# Sensor_Board.net
KiCad netlist of a schematic drawn in EAGLE
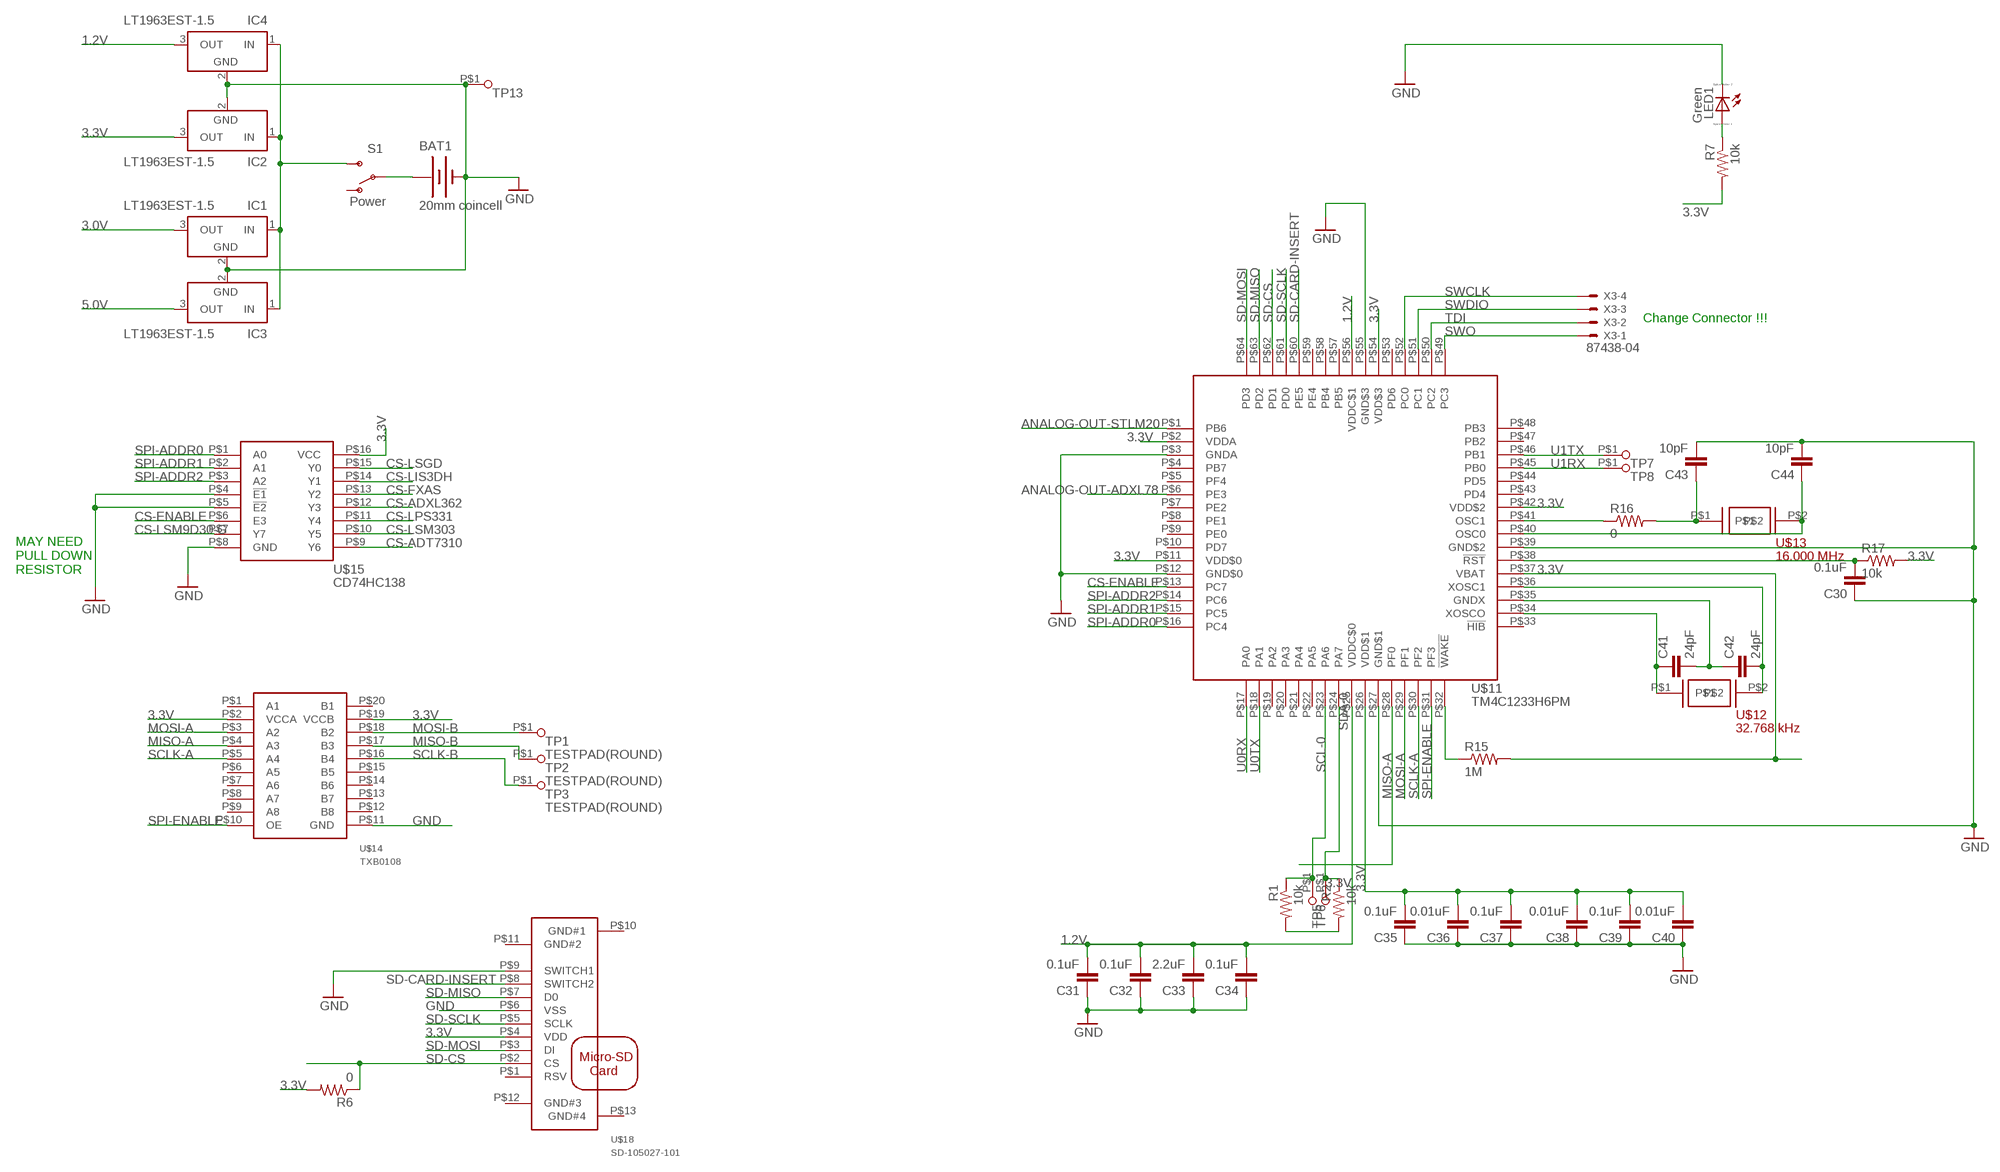
[diagram p0: schematic, sheet 1]
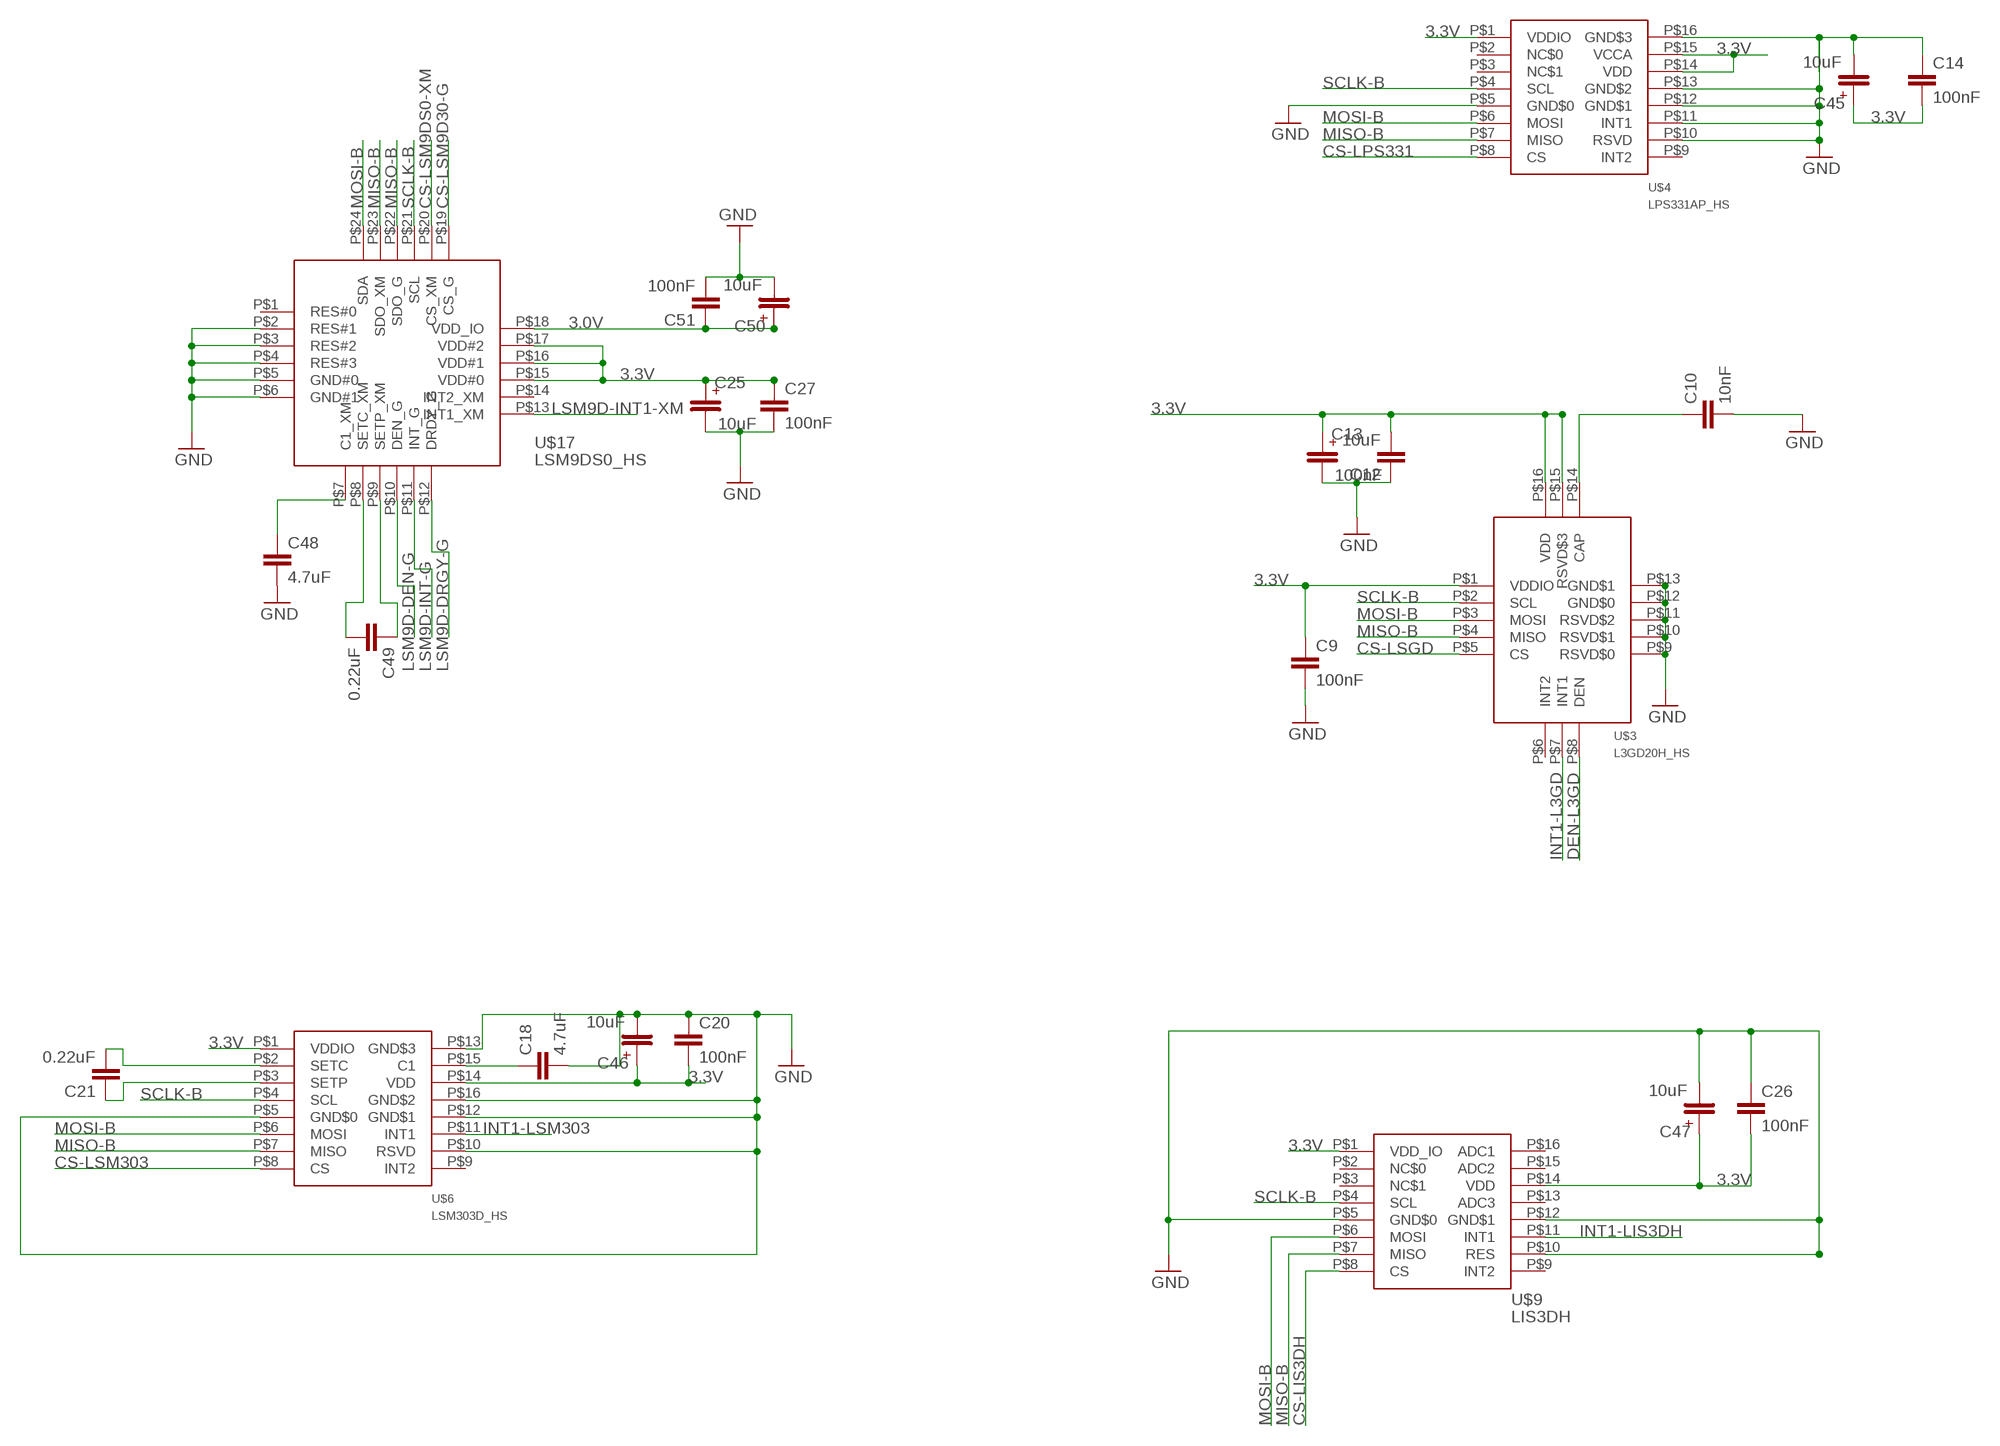
[diagram p1: schematic, sheet 2]
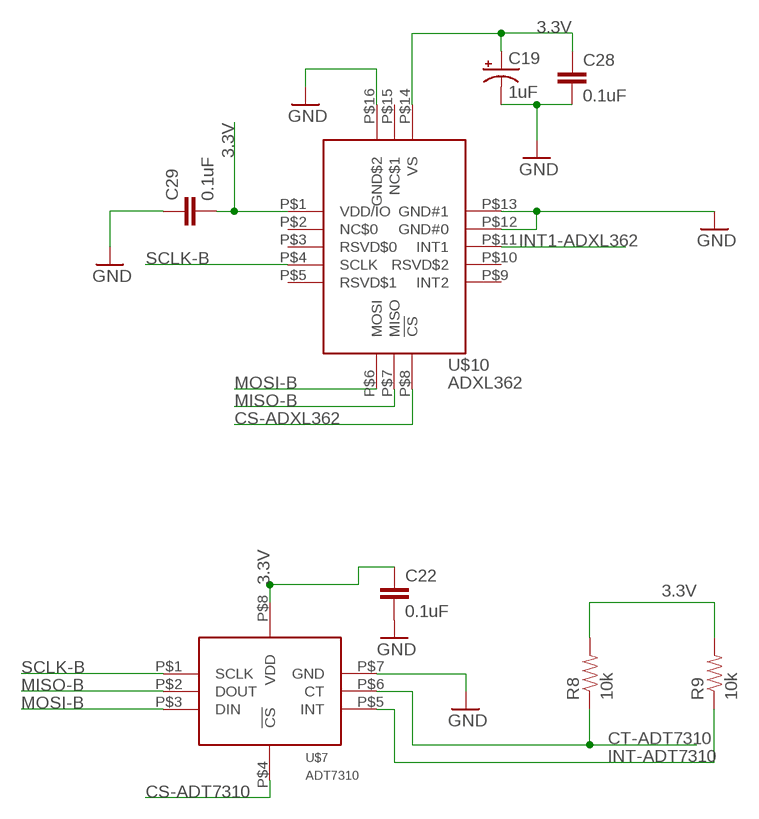
[diagram p2: schematic, sheet 3]
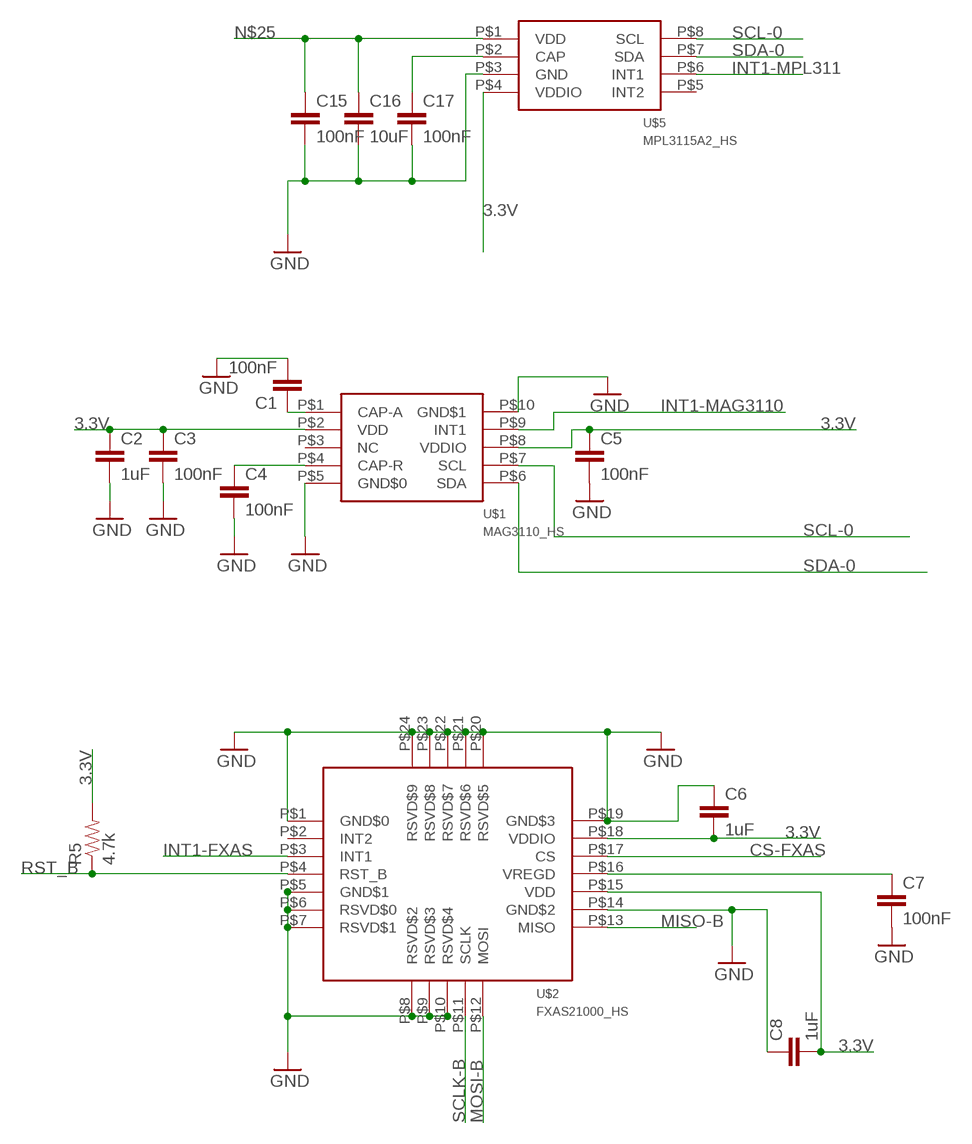
[diagram p3: schematic, sheet 4]
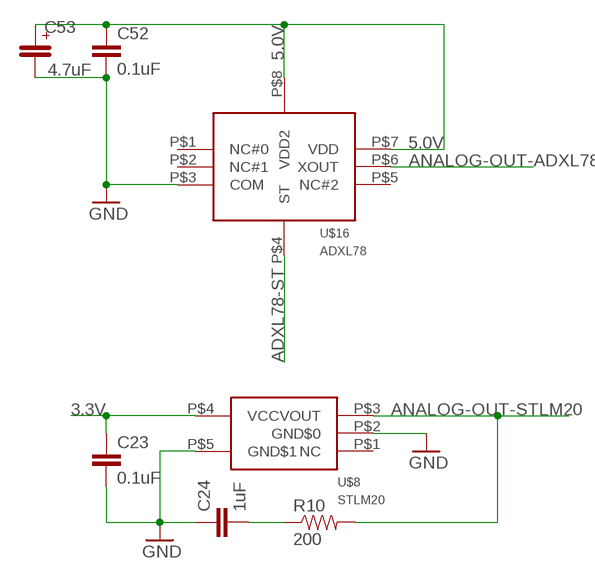
[diagram p4: schematic, sheet 5]

(export (version "E")
  (design (tool "Eeschema 10.0.6"))
  (components
    (comp (ref "C9")
      (value "100nF")
      (footprint "eagle-import:0603-CAP")
      (libsource (lib "eagle-import") (part "CAP0603-CAP"))
    )
    (comp (ref "C10")
      (value "10nF")
      (footprint "eagle-import:0603-CAP")
      (libsource (lib "eagle-import") (part "CAP0603-CAP"))
    )
    (comp (ref "C12")
      (value "10uF")
      (footprint "eagle-import:0603-CAP")
      (libsource (lib "eagle-import") (part "CAP0603-CAP"))
    )
    (comp (ref "C13")
      (value "100nF")
      (footprint "eagle-import:4.3X7.3SMD")
      (libsource (lib "eagle-import") (part "EEFCD0J100ER"))
    )
    (comp (ref "C14")
      (value "100nF")
      (footprint "eagle-import:0603-CAP")
      (libsource (lib "eagle-import") (part "CAP0603-CAP"))
    )
    (comp (ref "C18")
      (value "4.7uF")
      (footprint "eagle-import:0603-CAP")
      (libsource (lib "eagle-import") (part "CAP0603-CAP"))
    )
    (comp (ref "C20")
      (value "100nF")
      (footprint "eagle-import:0603-CAP")
      (libsource (lib "eagle-import") (part "CAP0603-CAP"))
    )
    (comp (ref "C21")
      (value "0.22uF")
      (footprint "eagle-import:0603-CAP")
      (libsource (lib "eagle-import") (part "CAP0603-CAP"))
    )
    (comp (ref "C25")
      (value "10uF")
      (footprint "eagle-import:4.3X7.3SMD")
      (libsource (lib "eagle-import") (part "EEFCD0J100ER"))
    )
    (comp (ref "C26")
      (value "100nF")
      (footprint "eagle-import:0603-CAP")
      (libsource (lib "eagle-import") (part "CAP0603-CAP"))
    )
    (comp (ref "C27")
      (value "100nF")
      (footprint "eagle-import:0603-CAP")
      (libsource (lib "eagle-import") (part "CAP0603-CAP"))
    )
    (comp (ref "C45")
      (value "10uF")
      (footprint "eagle-import:4.3X7.3SMD")
      (libsource (lib "eagle-import") (part "EEFCD0J100ER"))
    )
    (comp (ref "C46")
      (value "10uF")
      (footprint "eagle-import:4.3X7.3SMD")
      (libsource (lib "eagle-import") (part "EEFCD0J100ER"))
    )
    (comp (ref "C47")
      (value "10uF")
      (footprint "eagle-import:4.3X7.3SMD")
      (libsource (lib "eagle-import") (part "EEFCD0J100ER"))
    )
    (comp (ref "C48")
      (value "4.7uF")
      (footprint "eagle-import:0603-CAP")
      (libsource (lib "eagle-import") (part "CAP0603-CAP"))
    )
    (comp (ref "C49")
      (value "0.22uF")
      (footprint "eagle-import:0603-CAP")
      (libsource (lib "eagle-import") (part "CAP0603-CAP"))
    )
    (comp (ref "C50")
      (value "10uF")
      (footprint "eagle-import:4.3X7.3SMD")
      (libsource (lib "eagle-import") (part "EEFCD0J100ER"))
    )
    (comp (ref "C51")
      (value "100nF")
      (footprint "eagle-import:0603-CAP")
      (libsource (lib "eagle-import") (part "CAP0603-CAP"))
    )
    (comp (ref "U$3")
      (value "L3GD20H_HS")
      (footprint "eagle-import:LGA-16(3X3)_HS")
      (libsource (lib "eagle-import") (part "L3GD20H_HS"))
    )
    (comp (ref "U$4")
      (value "LPS331AP_HS")
      (footprint "eagle-import:LGA-16(3X3)_HS")
      (libsource (lib "eagle-import") (part "LPS331AP_HS"))
    )
    (comp (ref "U$6")
      (value "LSM303D_HS")
      (footprint "eagle-import:LGA-16(3X3)_HS")
      (libsource (lib "eagle-import") (part "LSM303D_HS"))
    )
    (comp (ref "U$9")
      (value "LIS3DH")
      (footprint "eagle-import:LGA-16(3X3)_HS")
      (libsource (lib "eagle-import") (part "LIS3DH_HS"))
    )
    (comp (ref "U$17")
      (value "LSM9DS0_HS")
      (footprint "eagle-import:LGA-24(4X4)_HS")
      (libsource (lib "eagle-import") (part "LSM9DS0_HS"))
    )
    (comp (ref "BAT1")
      (value "20mm coincell")
      (footprint "eagle-import:BATTCON_20MM_4LEGS")
      (libsource (lib "eagle-import") (part "BATTERY20MM_4LEGS"))
    )
    (comp (ref "C30")
      (value "0.1uF")
      (footprint "eagle-import:0603-CAP")
      (libsource (lib "eagle-import") (part "CAP0603-CAP"))
    )
    (comp (ref "C31")
      (value "0.1uF")
      (footprint "eagle-import:0603-CAP")
      (libsource (lib "eagle-import") (part "CAP0603-CAP"))
    )
    (comp (ref "C32")
      (value "0.1uF")
      (footprint "eagle-import:0603-CAP")
      (libsource (lib "eagle-import") (part "CAP0603-CAP"))
    )
    (comp (ref "C33")
      (value "2.2uF")
      (footprint "eagle-import:0603-CAP")
      (libsource (lib "eagle-import") (part "CAP0603-CAP"))
    )
    (comp (ref "C34")
      (value "0.1uF")
      (footprint "eagle-import:0603-CAP")
      (libsource (lib "eagle-import") (part "CAP0603-CAP"))
    )
    (comp (ref "C35")
      (value "0.1uF")
      (footprint "eagle-import:0603-CAP")
      (libsource (lib "eagle-import") (part "CAP0603-CAP"))
    )
    (comp (ref "C36")
      (value "0.01uF")
      (footprint "eagle-import:0603-CAP")
      (libsource (lib "eagle-import") (part "CAP0603-CAP"))
    )
    (comp (ref "C37")
      (value "0.1uF")
      (footprint "eagle-import:0603-CAP")
      (libsource (lib "eagle-import") (part "CAP0603-CAP"))
    )
    (comp (ref "C38")
      (value "0.01uF")
      (footprint "eagle-import:0603-CAP")
      (libsource (lib "eagle-import") (part "CAP0603-CAP"))
    )
    (comp (ref "C39")
      (value "0.1uF")
      (footprint "eagle-import:0603-CAP")
      (libsource (lib "eagle-import") (part "CAP0603-CAP"))
    )
    (comp (ref "C40")
      (value "0.01uF")
      (footprint "eagle-import:0603-CAP")
      (libsource (lib "eagle-import") (part "CAP0603-CAP"))
    )
    (comp (ref "C41")
      (value "24pF")
      (footprint "eagle-import:0603-CAP")
      (libsource (lib "eagle-import") (part "CAP0603-CAP"))
    )
    (comp (ref "C42")
      (value "24pF")
      (footprint "eagle-import:0603-CAP")
      (libsource (lib "eagle-import") (part "CAP0603-CAP"))
    )
    (comp (ref "C43")
      (value "10pF")
      (footprint "eagle-import:0603-CAP")
      (libsource (lib "eagle-import") (part "CAP0603-CAP"))
    )
    (comp (ref "C44")
      (value "10pF")
      (footprint "eagle-import:0603-CAP")
      (libsource (lib "eagle-import") (part "CAP0603-CAP"))
    )
    (comp (ref "IC1")
      (value "LT1963EST-1.5")
      (footprint "eagle-import:SOT223")
      (libsource (lib "eagle-import") (part "LT1963EST-1.5"))
    )
    (comp (ref "IC2")
      (value "LT1963EST-1.5")
      (footprint "eagle-import:SOT223")
      (libsource (lib "eagle-import") (part "LT1963EST-1.5"))
    )
    (comp (ref "IC3")
      (value "LT1963EST-1.5")
      (footprint "eagle-import:SOT223")
      (libsource (lib "eagle-import") (part "LT1963EST-1.5"))
    )
    (comp (ref "IC4")
      (value "LT1963EST-1.5")
      (footprint "eagle-import:SOT223")
      (libsource (lib "eagle-import") (part "LT1963EST-1.5"))
    )
    (comp (ref "LED1")
      (value "Green")
      (footprint "eagle-import:LED_SML0603")
      (libsource (lib "eagle-import") (part "LED_ESML0603"))
    )
    (comp (ref "R1")
      (value "10k")
      (footprint "eagle-import:0603-RES")
      (libsource (lib "eagle-import") (part "RESISTOR0603-RES"))
    )
    (comp (ref "R2")
      (value "10k")
      (footprint "eagle-import:0603-RES")
      (libsource (lib "eagle-import") (part "RESISTOR0603-RES"))
    )
    (comp (ref "R6")
      (value "0")
      (footprint "eagle-import:0603-RES")
      (libsource (lib "eagle-import") (part "RESISTOR0603-RES"))
    )
    (comp (ref "R7")
      (value "10k")
      (footprint "eagle-import:0603-RES")
      (libsource (lib "eagle-import") (part "RESISTOR0603-RES"))
    )
    (comp (ref "R15")
      (value "1M")
      (footprint "eagle-import:0603-RES")
      (libsource (lib "eagle-import") (part "RESISTOR0603-RES"))
    )
    (comp (ref "R16")
      (value "0")
      (footprint "eagle-import:0603-RES")
      (libsource (lib "eagle-import") (part "RESISTOR0603-RES"))
    )
    (comp (ref "R17")
      (value "10k")
      (footprint "eagle-import:0603-RES")
      (libsource (lib "eagle-import") (part "RESISTOR0603-RES"))
    )
    (comp (ref "S1")
      (value "Power")
      (footprint "eagle-import:SWITCH-SPST-SMD-A")
      (libsource (lib "eagle-import") (part "SWITCH-SPDT-SMD-A"))
    )
    (comp (ref "TP1")
      (value "TESTPAD(ROUND)")
      (footprint "eagle-import:TESTPAD(ROUND)")
      (libsource (lib "eagle-import") (part "TESTPAD(ROUND)"))
    )
    (comp (ref "TP2")
      (value "TESTPAD(ROUND)")
      (footprint "eagle-import:TESTPAD(ROUND)")
      (libsource (lib "eagle-import") (part "TESTPAD(ROUND)"))
    )
    (comp (ref "TP3")
      (value "TESTPAD(ROUND)")
      (footprint "eagle-import:TESTPAD(ROUND)")
      (libsource (lib "eagle-import") (part "TESTPAD(ROUND)"))
    )
    (comp (ref "TP5")
      (value "TESTPAD(ROUND)")
      (footprint "eagle-import:TESTPAD(ROUND)")
      (libsource (lib "eagle-import") (part "TESTPAD(ROUND)"))
    )
    (comp (ref "TP6")
      (value "TESTPAD(ROUND)")
      (footprint "eagle-import:TESTPAD(ROUND)")
      (libsource (lib "eagle-import") (part "TESTPAD(ROUND)"))
    )
    (comp (ref "TP7")
      (value "TESTPAD(ROUND)")
      (footprint "eagle-import:TESTPAD(ROUND)")
      (libsource (lib "eagle-import") (part "TESTPAD(ROUND)"))
    )
    (comp (ref "TP8")
      (value "TESTPAD(ROUND)")
      (footprint "eagle-import:TESTPAD(ROUND)")
      (libsource (lib "eagle-import") (part "TESTPAD(ROUND)"))
    )
    (comp (ref "TP13")
      (value "TESTPAD(ROUND)")
      (footprint "eagle-import:TESTPAD(ROUND)")
      (libsource (lib "eagle-import") (part "TESTPAD(ROUND)"))
    )
    (comp (ref "U$11")
      (value "TM4C1233H6PM")
      (footprint "eagle-import:S-PQFP-G64")
      (libsource (lib "eagle-import") (part "TM4C1233H6PM"))
    )
    (comp (ref "U$12")
      (value "32.768 kHz")
      (footprint "eagle-import:CYLINDRICAL-(1.9DIAX6L)")
      (libsource (lib "eagle-import") (part "AB26TRB"))
    )
    (comp (ref "U$13")
      (value "16.000 MHz")
      (footprint "eagle-import:2-SMD")
      (libsource (lib "eagle-import") (part "NX5032GA"))
    )
    (comp (ref "U$14")
      (value "TXB0108")
      (footprint "eagle-import:TSSOP-(PW)-20")
      (libsource (lib "eagle-import") (part "TXB0108"))
    )
    (comp (ref "U$15")
      (value "CD74HC138")
      (footprint "eagle-import:SOIC-16")
      (libsource (lib "eagle-import") (part "CD74HC138"))
    )
    (comp (ref "U$18")
      (value "SD-105027-101")
      (footprint "eagle-import:SD-105027-101")
      (libsource (lib "eagle-import") (part "SD-105027-101"))
    )
    (comp (ref "X3")
      (value "87438-04")
      (footprint "eagle-import:87438-04")
      (libsource (lib "eagle-import") (part "87438-04"))
    )
    (comp (ref "C1")
      (value "100nF")
      (footprint "eagle-import:0603-CAP")
      (libsource (lib "eagle-import") (part "CAP0603-CAP"))
    )
    (comp (ref "C2")
      (value "1uF")
      (footprint "eagle-import:0603-CAP")
      (libsource (lib "eagle-import") (part "CAP0603-CAP"))
    )
    (comp (ref "C3")
      (value "100nF")
      (footprint "eagle-import:0603-CAP")
      (libsource (lib "eagle-import") (part "CAP0603-CAP"))
    )
    (comp (ref "C4")
      (value "100nF")
      (footprint "eagle-import:0603-CAP")
      (libsource (lib "eagle-import") (part "CAP0603-CAP"))
    )
    (comp (ref "C5")
      (value "100nF")
      (footprint "eagle-import:0603-CAP")
      (libsource (lib "eagle-import") (part "CAP0603-CAP"))
    )
    (comp (ref "C6")
      (value "1uF")
      (footprint "eagle-import:0603-CAP")
      (libsource (lib "eagle-import") (part "CAP0603-CAP"))
    )
    (comp (ref "C7")
      (value "100nF")
      (footprint "eagle-import:0603-CAP")
      (libsource (lib "eagle-import") (part "CAP0603-CAP"))
    )
    (comp (ref "C8")
      (value "1uF")
      (footprint "eagle-import:0603-CAP")
      (libsource (lib "eagle-import") (part "CAP0603-CAP"))
    )
    (comp (ref "C15")
      (value "100nF")
      (footprint "eagle-import:0603-CAP")
      (libsource (lib "eagle-import") (part "CAP0603-CAP"))
    )
    (comp (ref "C16")
      (value "10uF")
      (footprint "eagle-import:0603-CAP")
      (libsource (lib "eagle-import") (part "CAP0603-CAP"))
    )
    (comp (ref "C17")
      (value "100nF")
      (footprint "eagle-import:0603-CAP")
      (libsource (lib "eagle-import") (part "CAP0603-CAP"))
    )
    (comp (ref "R5")
      (value "4.7k")
      (footprint "eagle-import:0603-RES")
      (libsource (lib "eagle-import") (part "RESISTOR0603-RES"))
    )
    (comp (ref "U$1")
      (value "MAG3110_HS")
      (footprint "eagle-import:DFN-10(2X2)_HS")
      (libsource (lib "eagle-import") (part "MAG3110_HS"))
    )
    (comp (ref "U$2")
      (value "FXAS21000_HS")
      (footprint "eagle-import:QFN-24(4X4)_HS")
      (libsource (lib "eagle-import") (part "FXAS21000_HS"))
    )
    (comp (ref "U$5")
      (value "MPL3115A2_HS")
      (footprint "eagle-import:LGA-8(5X3)_HS")
      (libsource (lib "eagle-import") (part "MPL3115A2_HS"))
    )
    (comp (ref "C19")
      (value "1uF")
      (footprint "eagle-import:EIA6032")
      (libsource (lib "eagle-import") (part "CAP_POL6032"))
    )
    (comp (ref "C22")
      (value "0.1uF")
      (footprint "eagle-import:0603-CAP")
      (libsource (lib "eagle-import") (part "CAP0603-CAP"))
    )
    (comp (ref "C28")
      (value "0.1uF")
      (footprint "eagle-import:0603-CAP")
      (libsource (lib "eagle-import") (part "CAP0603-CAP"))
    )
    (comp (ref "C29")
      (value "0.1uF")
      (footprint "eagle-import:0603-CAP")
      (libsource (lib "eagle-import") (part "CAP0603-CAP"))
    )
    (comp (ref "R8")
      (value "10k")
      (footprint "eagle-import:0603-RES")
      (libsource (lib "eagle-import") (part "RESISTOR0603-RES"))
    )
    (comp (ref "R9")
      (value "10k")
      (footprint "eagle-import:0603-RES")
      (libsource (lib "eagle-import") (part "RESISTOR0603-RES"))
    )
    (comp (ref "U$7")
      (value "ADT7310")
      (footprint "eagle-import:SOIC-8(5X6.2)")
      (libsource (lib "eagle-import") (part "ADT7310"))
    )
    (comp (ref "U$10")
      (value "ADXL362")
      (footprint "eagle-import:LGA-16(3X3.25)_HS")
      (libsource (lib "eagle-import") (part "ADXL362_HS"))
    )
    (comp (ref "C23")
      (value "0.1uF")
      (footprint "eagle-import:0603-CAP")
      (libsource (lib "eagle-import") (part "CAP0603-CAP"))
    )
    (comp (ref "C24")
      (value "1uF")
      (footprint "eagle-import:0603-CAP")
      (libsource (lib "eagle-import") (part "CAP0603-CAP"))
    )
    (comp (ref "C52")
      (value "0.1uF")
      (footprint "eagle-import:0603-CAP")
      (libsource (lib "eagle-import") (part "CAP0603-CAP"))
    )
    (comp (ref "C53")
      (value "4.7uF")
      (footprint "eagle-import:4.3X7.3SMD")
      (libsource (lib "eagle-import") (part "EEFCD0J100ER"))
    )
    (comp (ref "R10")
      (value "200")
      (footprint "eagle-import:0603-RES")
      (libsource (lib "eagle-import") (part "RESISTOR0603-RES"))
    )
    (comp (ref "U$8")
      (value "STLM20")
      (footprint "eagle-import:SOT323-5L")
      (libsource (lib "eagle-import") (part "STLM20"))
    )
    (comp (ref "U$16")
      (value "ADXL78")
      (footprint "eagle-import:LCC-8(5X5)_HS")
      (libsource (lib "eagle-import") (part "ADXL78"))
    )
  )
  (nets
    (net (code "1") (name "1.2V") (class "Default")
      (node (ref "C31") (pin "2") (pinfunction "2_2") (pintype "passive"))
      (node (ref "C32") (pin "2") (pinfunction "2_2") (pintype "passive"))
      (node (ref "C33") (pin "2") (pinfunction "2_2") (pintype "passive"))
      (node (ref "C34") (pin "2") (pinfunction "2_2") (pintype "passive"))
      (node (ref "IC4") (pin "3") (pinfunction "OUT_3") (pintype "output"))
      (node (ref "U$11") (pin "P$25") (pinfunction "VDDC$0_P$25") (pintype "bidirectional"))
      (node (ref "U$11") (pin "P$56") (pinfunction "VDDC$1_P$56") (pintype "bidirectional"))
    )
    (net (code "2") (name "3.0V") (class "Default")
      (node (ref "C50") (pin "P$1") (pintype "bidirectional"))
      (node (ref "C51") (pin "1") (pinfunction "1_1") (pintype "passive"))
      (node (ref "IC1") (pin "3") (pinfunction "OUT_3") (pintype "output"))
      (node (ref "U$17") (pin "P$18") (pinfunction "VDD_IO_P$18") (pintype "bidirectional"))
    )
    (net (code "3") (name "3.3V") (class "Default")
      (node (ref "C12") (pin "2") (pinfunction "2_2") (pintype "passive"))
      (node (ref "C13") (pin "P$1") (pintype "bidirectional"))
      (node (ref "C14") (pin "2") (pinfunction "2_2") (pintype "passive"))
      (node (ref "C19") (pin "P$1") (pinfunction "+_P$1") (pintype "passive"))
      (node (ref "C2") (pin "1") (pinfunction "1_1") (pintype "passive"))
      (node (ref "C20") (pin "2") (pinfunction "2_2") (pintype "passive"))
      (node (ref "C22") (pin "1") (pinfunction "1_1") (pintype "passive"))
      (node (ref "C23") (pin "1") (pinfunction "1_1") (pintype "passive"))
      (node (ref "C25") (pin "P$1") (pintype "bidirectional"))
      (node (ref "C26") (pin "2") (pinfunction "2_2") (pintype "passive"))
      (node (ref "C27") (pin "1") (pinfunction "1_1") (pintype "passive"))
      (node (ref "C28") (pin "1") (pinfunction "1_1") (pintype "passive"))
      (node (ref "C29") (pin "2") (pinfunction "2_2") (pintype "passive"))
      (node (ref "C3") (pin "1") (pinfunction "1_1") (pintype "passive"))
      (node (ref "C35") (pin "2") (pinfunction "2_2") (pintype "passive"))
      (node (ref "C36") (pin "2") (pinfunction "2_2") (pintype "passive"))
      (node (ref "C37") (pin "2") (pinfunction "2_2") (pintype "passive"))
      (node (ref "C38") (pin "2") (pinfunction "2_2") (pintype "passive"))
      (node (ref "C39") (pin "2") (pinfunction "2_2") (pintype "passive"))
      (node (ref "C40") (pin "2") (pinfunction "2_2") (pintype "passive"))
      (node (ref "C45") (pin "P$1") (pintype "bidirectional"))
      (node (ref "C46") (pin "P$1") (pintype "bidirectional"))
      (node (ref "C47") (pin "P$1") (pintype "bidirectional"))
      (node (ref "C5") (pin "1") (pinfunction "1_1") (pintype "passive"))
      (node (ref "C6") (pin "2") (pinfunction "2_2") (pintype "passive"))
      (node (ref "C8") (pin "2") (pinfunction "2_2") (pintype "passive"))
      (node (ref "C9") (pin "1") (pinfunction "1_1") (pintype "passive"))
      (node (ref "IC2") (pin "3") (pinfunction "OUT_3") (pintype "output"))
      (node (ref "R1") (pin "2") (pinfunction "2_2") (pintype "passive"))
      (node (ref "R15") (pin "2") (pinfunction "2_2") (pintype "passive"))
      (node (ref "R17") (pin "2") (pinfunction "2_2") (pintype "passive"))
      (node (ref "R2") (pin "2") (pinfunction "2_2") (pintype "passive"))
      (node (ref "R5") (pin "2") (pinfunction "2_2") (pintype "passive"))
      (node (ref "R6") (pin "2") (pinfunction "2_2") (pintype "passive"))
      (node (ref "R7") (pin "2") (pinfunction "2_2") (pintype "passive"))
      (node (ref "R8") (pin "2") (pinfunction "2_2") (pintype "passive"))
      (node (ref "R9") (pin "2") (pinfunction "2_2") (pintype "passive"))
      (node (ref "U$1") (pin "P$2") (pinfunction "VDD_P$2") (pintype "bidirectional"))
      (node (ref "U$1") (pin "P$8") (pinfunction "VDDIO_P$8") (pintype "bidirectional"))
      (node (ref "U$10") (pin "P$1") (pinfunction "VDD/IO_P$1") (pintype "bidirectional"))
      (node (ref "U$10") (pin "P$14") (pinfunction "VS_P$14") (pintype "bidirectional"))
      (node (ref "U$11") (pin "P$11") (pinfunction "VDD$0_P$11") (pintype "bidirectional"))
      (node (ref "U$11") (pin "P$2") (pinfunction "VDDA_P$2") (pintype "bidirectional"))
      (node (ref "U$11") (pin "P$26") (pinfunction "VDD$1_P$26") (pintype "bidirectional"))
      (node (ref "U$11") (pin "P$37") (pinfunction "VBAT_P$37") (pintype "bidirectional"))
      (node (ref "U$11") (pin "P$42") (pinfunction "VDD$2_P$42") (pintype "bidirectional"))
      (node (ref "U$11") (pin "P$54") (pinfunction "VDD$3_P$54") (pintype "bidirectional"))
      (node (ref "U$14") (pin "P$19") (pinfunction "VCCB_P$19") (pintype "bidirectional"))
      (node (ref "U$14") (pin "P$2") (pinfunction "VCCA_P$2") (pintype "bidirectional"))
      (node (ref "U$15") (pin "P$16") (pinfunction "VCC_P$16") (pintype "bidirectional"))
      (node (ref "U$17") (pin "P$15") (pinfunction "VDD#0_P$15") (pintype "bidirectional"))
      (node (ref "U$17") (pin "P$16") (pinfunction "VDD#1_P$16") (pintype "bidirectional"))
      (node (ref "U$17") (pin "P$17") (pinfunction "VDD#2_P$17") (pintype "bidirectional"))
      (node (ref "U$18") (pin "P$4") (pinfunction "VDD_P$4") (pintype "bidirectional"))
      (node (ref "U$2") (pin "P$15") (pinfunction "VDD_P$15") (pintype "bidirectional"))
      (node (ref "U$2") (pin "P$18") (pinfunction "VDDIO_P$18") (pintype "bidirectional"))
      (node (ref "U$3") (pin "P$1") (pinfunction "VDDIO_P$1") (pintype "bidirectional"))
      (node (ref "U$3") (pin "P$15") (pinfunction "RSVD$3_P$15") (pintype "bidirectional"))
      (node (ref "U$3") (pin "P$16") (pinfunction "VDD_P$16") (pintype "bidirectional"))
      (node (ref "U$4") (pin "P$1") (pinfunction "VDDIO_P$1") (pintype "bidirectional"))
      (node (ref "U$4") (pin "P$14") (pinfunction "VDD_P$14") (pintype "bidirectional"))
      (node (ref "U$4") (pin "P$15") (pinfunction "VCCA_P$15") (pintype "bidirectional"))
      (node (ref "U$5") (pin "P$4") (pinfunction "VDDIO_P$4") (pintype "bidirectional"))
      (node (ref "U$6") (pin "P$1") (pinfunction "VDDIO_P$1") (pintype "bidirectional"))
      (node (ref "U$6") (pin "P$14") (pinfunction "VDD_P$14") (pintype "bidirectional"))
      (node (ref "U$7") (pin "P$8") (pinfunction "VDD_P$8") (pintype "bidirectional"))
      (node (ref "U$8") (pin "P$4") (pinfunction "VCC_P$4") (pintype "bidirectional"))
      (node (ref "U$9") (pin "P$1") (pinfunction "VDD_IO_P$1") (pintype "bidirectional"))
      (node (ref "U$9") (pin "P$14") (pinfunction "VDD_P$14") (pintype "bidirectional"))
    )
    (net (code "4") (name "5.0V") (class "Default")
      (node (ref "C52") (pin "1") (pinfunction "1_1") (pintype "passive"))
      (node (ref "C53") (pin "P$1") (pintype "bidirectional"))
      (node (ref "IC3") (pin "3") (pinfunction "OUT_3") (pintype "output"))
      (node (ref "U$16") (pin "P$7") (pinfunction "VDD_P$7") (pintype "bidirectional"))
      (node (ref "U$16") (pin "P$8") (pinfunction "VDD2_P$8") (pintype "bidirectional"))
    )
    (net (code "5") (name "ADXL78-ST") (class "Default")
      (node (ref "U$16") (pin "P$4") (pinfunction "ST_P$4") (pintype "bidirectional"))
    )
    (net (code "6") (name "ANALOG-OUT-ADXL78") (class "Default")
      (node (ref "U$11") (pin "P$6") (pinfunction "PE3_P$6") (pintype "bidirectional"))
      (node (ref "U$16") (pin "P$6") (pinfunction "XOUT_P$6") (pintype "bidirectional"))
    )
    (net (code "7") (name "ANALOG-OUT-STLM20") (class "Default")
      (node (ref "R10") (pin "2") (pinfunction "2_2") (pintype "passive"))
      (node (ref "U$11") (pin "P$1") (pinfunction "PB6_P$1") (pintype "bidirectional"))
      (node (ref "U$8") (pin "P$3") (pinfunction "VOUT_P$3") (pintype "bidirectional"))
    )
    (net (code "8") (name "CS-ADT7310") (class "Default")
      (node (ref "U$15") (pin "P$9") (pinfunction "Y6_P$9") (pintype "bidirectional"))
      (node (ref "U$7") (pin "P$4") (pinfunction "~{CS}_P$4") (pintype "bidirectional"))
    )
    (net (code "9") (name "CS-ADXL362") (class "Default")
      (node (ref "U$10") (pin "P$8") (pinfunction "~{CS}_P$8") (pintype "bidirectional"))
      (node (ref "U$15") (pin "P$12") (pinfunction "Y3_P$12") (pintype "bidirectional"))
    )
    (net (code "10") (name "CS-ENABLE") (class "Default")
      (node (ref "U$11") (pin "P$13") (pinfunction "PC7_P$13") (pintype "bidirectional"))
      (node (ref "U$15") (pin "P$6") (pinfunction "E3_P$6") (pintype "bidirectional"))
    )
    (net (code "11") (name "CS-FXAS") (class "Default")
      (node (ref "U$15") (pin "P$13") (pinfunction "Y2_P$13") (pintype "bidirectional"))
      (node (ref "U$2") (pin "P$17") (pinfunction "CS_P$17") (pintype "bidirectional"))
    )
    (net (code "12") (name "CS-LIS3DH") (class "Default")
      (node (ref "U$15") (pin "P$14") (pinfunction "Y1_P$14") (pintype "bidirectional"))
      (node (ref "U$9") (pin "P$8") (pinfunction "CS_P$8") (pintype "bidirectional"))
    )
    (net (code "13") (name "CS-LPS331") (class "Default")
      (node (ref "U$15") (pin "P$11") (pinfunction "Y4_P$11") (pintype "bidirectional"))
      (node (ref "U$4") (pin "P$8") (pinfunction "CS_P$8") (pintype "bidirectional"))
    )
    (net (code "14") (name "CS-LSGD") (class "Default")
      (node (ref "U$15") (pin "P$15") (pinfunction "Y0_P$15") (pintype "bidirectional"))
      (node (ref "U$3") (pin "P$5") (pinfunction "CS_P$5") (pintype "bidirectional"))
    )
    (net (code "15") (name "CS-LSM9D30-G") (class "Default")
      (node (ref "U$15") (pin "P$7") (pinfunction "Y7_P$7") (pintype "bidirectional"))
      (node (ref "U$17") (pin "P$19") (pinfunction "CS_G_P$19") (pintype "bidirectional"))
    )
    (net (code "16") (name "CS-LSM9DS0-XM") (class "Default")
      (node (ref "U$17") (pin "P$20") (pinfunction "CS_XM_P$20") (pintype "bidirectional"))
    )
    (net (code "17") (name "CS-LSM303") (class "Default")
      (node (ref "U$15") (pin "P$10") (pinfunction "Y5_P$10") (pintype "bidirectional"))
      (node (ref "U$6") (pin "P$8") (pinfunction "CS_P$8") (pintype "bidirectional"))
    )
    (net (code "18") (name "CT-ADT7310") (class "Default")
      (node (ref "R8") (pin "1") (pinfunction "1_1") (pintype "passive"))
      (node (ref "U$7") (pin "P$6") (pinfunction "CT_P$6") (pintype "bidirectional"))
    )
    (net (code "19") (name "DEN-L3GD") (class "Default")
      (node (ref "U$3") (pin "P$8") (pinfunction "DEN_P$8") (pintype "bidirectional"))
    )
    (net (code "20") (name "GND") (class "Default")
      (node (ref "BAT1") (pin "2") (pinfunction "-_2") (pintype "power_in"))
      (node (ref "C1") (pin "2") (pinfunction "2_2") (pintype "passive"))
      (node (ref "C10") (pin "2") (pinfunction "2_2") (pintype "passive"))
      (node (ref "C12") (pin "1") (pinfunction "1_1") (pintype "passive"))
      (node (ref "C13") (pin "P$2") (pintype "bidirectional"))
      (node (ref "C14") (pin "1") (pinfunction "1_1") (pintype "passive"))
      (node (ref "C15") (pin "2") (pinfunction "2_2") (pintype "passive"))
      (node (ref "C16") (pin "2") (pinfunction "2_2") (pintype "passive"))
      (node (ref "C17") (pin "2") (pinfunction "2_2") (pintype "passive"))
      (node (ref "C18") (pin "2") (pinfunction "2_2") (pintype "passive"))
      (node (ref "C19") (pin "P$2") (pinfunction "-_P$2") (pintype "passive"))
      (node (ref "C2") (pin "2") (pinfunction "2_2") (pintype "passive"))
      (node (ref "C20") (pin "1") (pinfunction "1_1") (pintype "passive"))
      (node (ref "C22") (pin "2") (pinfunction "2_2") (pintype "passive"))
      (node (ref "C23") (pin "2") (pinfunction "2_2") (pintype "passive"))
      (node (ref "C24") (pin "1") (pinfunction "1_1") (pintype "passive"))
      (node (ref "C25") (pin "P$2") (pintype "bidirectional"))
      (node (ref "C26") (pin "1") (pinfunction "1_1") (pintype "passive"))
      (node (ref "C27") (pin "2") (pinfunction "2_2") (pintype "passive"))
      (node (ref "C28") (pin "2") (pinfunction "2_2") (pintype "passive"))
      (node (ref "C29") (pin "1") (pinfunction "1_1") (pintype "passive"))
      (node (ref "C3") (pin "2") (pinfunction "2_2") (pintype "passive"))
      (node (ref "C30") (pin "1") (pinfunction "1_1") (pintype "passive"))
      (node (ref "C31") (pin "1") (pinfunction "1_1") (pintype "passive"))
      (node (ref "C32") (pin "1") (pinfunction "1_1") (pintype "passive"))
      (node (ref "C33") (pin "1") (pinfunction "1_1") (pintype "passive"))
      (node (ref "C34") (pin "1") (pinfunction "1_1") (pintype "passive"))
      (node (ref "C35") (pin "1") (pinfunction "1_1") (pintype "passive"))
      (node (ref "C36") (pin "1") (pinfunction "1_1") (pintype "passive"))
      (node (ref "C37") (pin "1") (pinfunction "1_1") (pintype "passive"))
      (node (ref "C38") (pin "1") (pinfunction "1_1") (pintype "passive"))
      (node (ref "C39") (pin "1") (pinfunction "1_1") (pintype "passive"))
      (node (ref "C4") (pin "2") (pinfunction "2_2") (pintype "passive"))
      (node (ref "C40") (pin "1") (pinfunction "1_1") (pintype "passive"))
      (node (ref "C43") (pin "2") (pinfunction "2_2") (pintype "passive"))
      (node (ref "C44") (pin "2") (pinfunction "2_2") (pintype "passive"))
      (node (ref "C45") (pin "P$2") (pintype "bidirectional"))
      (node (ref "C46") (pin "P$2") (pintype "bidirectional"))
      (node (ref "C47") (pin "P$2") (pintype "bidirectional"))
      (node (ref "C48") (pin "2") (pinfunction "2_2") (pintype "passive"))
      (node (ref "C5") (pin "2") (pinfunction "2_2") (pintype "passive"))
      (node (ref "C50") (pin "P$2") (pintype "bidirectional"))
      (node (ref "C51") (pin "2") (pinfunction "2_2") (pintype "passive"))
      (node (ref "C52") (pin "2") (pinfunction "2_2") (pintype "passive"))
      (node (ref "C53") (pin "P$2") (pintype "bidirectional"))
      (node (ref "C6") (pin "1") (pinfunction "1_1") (pintype "passive"))
      (node (ref "C7") (pin "2") (pinfunction "2_2") (pintype "passive"))
      (node (ref "C8") (pin "1") (pinfunction "1_1") (pintype "passive"))
      (node (ref "C9") (pin "2") (pinfunction "2_2") (pintype "passive"))
      (node (ref "IC1") (pin "2") (pinfunction "GND_2") (pintype "power_in"))
      (node (ref "IC2") (pin "2") (pinfunction "GND_2") (pintype "power_in"))
      (node (ref "IC3") (pin "2") (pinfunction "GND_2") (pintype "power_in"))
      (node (ref "IC4") (pin "2") (pinfunction "GND_2") (pintype "power_in"))
      (node (ref "LED1") (pin "C") (pinfunction "C_C") (pintype "passive"))
      (node (ref "TP13") (pin "P$1") (pinfunction "P$1_P$1") (pintype "bidirectional"))
      (node (ref "U$1") (pin "P$10") (pinfunction "GND$1_P$10") (pintype "bidirectional"))
      (node (ref "U$1") (pin "P$5") (pinfunction "GND$0_P$5") (pintype "bidirectional"))
      (node (ref "U$10") (pin "P$12") (pinfunction "GND#0_P$12") (pintype "bidirectional"))
      (node (ref "U$10") (pin "P$13") (pinfunction "GND#1_P$13") (pintype "bidirectional"))
      (node (ref "U$10") (pin "P$16") (pinfunction "GND$2_P$16") (pintype "bidirectional"))
      (node (ref "U$11") (pin "P$12") (pinfunction "GND$0_P$12") (pintype "bidirectional"))
      (node (ref "U$11") (pin "P$27") (pinfunction "GND$1_P$27") (pintype "bidirectional"))
      (node (ref "U$11") (pin "P$3") (pinfunction "GNDA_P$3") (pintype "bidirectional"))
      (node (ref "U$11") (pin "P$39") (pinfunction "GND$2_P$39") (pintype "bidirectional"))
      (node (ref "U$11") (pin "P$55") (pinfunction "GND$3_P$55") (pintype "bidirectional"))
      (node (ref "U$14") (pin "P$11") (pinfunction "GND_P$11") (pintype "bidirectional"))
      (node (ref "U$15") (pin "P$4") (pinfunction "~{E1}_P$4") (pintype "bidirectional"))
      (node (ref "U$15") (pin "P$5") (pinfunction "~{E2}_P$5") (pintype "bidirectional"))
      (node (ref "U$15") (pin "P$8") (pinfunction "GND_P$8") (pintype "bidirectional"))
      (node (ref "U$16") (pin "P$3") (pinfunction "COM_P$3") (pintype "bidirectional"))
      (node (ref "U$17") (pin "P$2") (pinfunction "RES#1_P$2") (pintype "bidirectional"))
      (node (ref "U$17") (pin "P$3") (pinfunction "RES#2_P$3") (pintype "bidirectional"))
      (node (ref "U$17") (pin "P$4") (pinfunction "RES#3_P$4") (pintype "bidirectional"))
      (node (ref "U$17") (pin "P$5") (pinfunction "GND#0_P$5") (pintype "bidirectional"))
      (node (ref "U$17") (pin "P$6") (pinfunction "GND#1_P$6") (pintype "bidirectional"))
      (node (ref "U$18") (pin "P$6") (pinfunction "VSS_P$6") (pintype "bidirectional"))
      (node (ref "U$18") (pin "P$9") (pinfunction "SWITCH1_P$9") (pintype "bidirectional"))
      (node (ref "U$2") (pin "P$1") (pinfunction "GND$0_P$1") (pintype "bidirectional"))
      (node (ref "U$2") (pin "P$10") (pinfunction "RSVD$4_P$10") (pintype "bidirectional"))
      (node (ref "U$2") (pin "P$14") (pinfunction "GND$2_P$14") (pintype "bidirectional"))
      (node (ref "U$2") (pin "P$19") (pinfunction "GND$3_P$19") (pintype "bidirectional"))
      (node (ref "U$2") (pin "P$20") (pinfunction "RSVD$5_P$20") (pintype "bidirectional"))
      (node (ref "U$2") (pin "P$21") (pinfunction "RSVD$6_P$21") (pintype "bidirectional"))
      (node (ref "U$2") (pin "P$22") (pinfunction "RSVD$7_P$22") (pintype "bidirectional"))
      (node (ref "U$2") (pin "P$23") (pinfunction "RSVD$8_P$23") (pintype "bidirectional"))
      (node (ref "U$2") (pin "P$24") (pinfunction "RSVD$9_P$24") (pintype "bidirectional"))
      (node (ref "U$2") (pin "P$5") (pinfunction "GND$1_P$5") (pintype "bidirectional"))
      (node (ref "U$2") (pin "P$6") (pinfunction "RSVD$0_P$6") (pintype "bidirectional"))
      (node (ref "U$2") (pin "P$7") (pinfunction "RSVD$1_P$7") (pintype "bidirectional"))
      (node (ref "U$2") (pin "P$8") (pinfunction "RSVD$2_P$8") (pintype "bidirectional"))
      (node (ref "U$2") (pin "P$9") (pinfunction "RSVD$3_P$9") (pintype "bidirectional"))
      (node (ref "U$3") (pin "P$10") (pinfunction "RSVD$1_P$10") (pintype "bidirectional"))
      (node (ref "U$3") (pin "P$11") (pinfunction "RSVD$2_P$11") (pintype "bidirectional"))
      (node (ref "U$3") (pin "P$12") (pinfunction "GND$0_P$12") (pintype "bidirectional"))
      (node (ref "U$3") (pin "P$13") (pinfunction "GND$1_P$13") (pintype "bidirectional"))
      (node (ref "U$3") (pin "P$9") (pinfunction "RSVD$0_P$9") (pintype "bidirectional"))
      (node (ref "U$4") (pin "P$10") (pinfunction "RSVD_P$10") (pintype "bidirectional"))
      (node (ref "U$4") (pin "P$11") (pinfunction "INT1_P$11") (pintype "bidirectional"))
      (node (ref "U$4") (pin "P$12") (pinfunction "GND$1_P$12") (pintype "bidirectional"))
      (node (ref "U$4") (pin "P$13") (pinfunction "GND$2_P$13") (pintype "bidirectional"))
      (node (ref "U$4") (pin "P$16") (pinfunction "GND$3_P$16") (pintype "bidirectional"))
      (node (ref "U$4") (pin "P$5") (pinfunction "GND$0_P$5") (pintype "bidirectional"))
      (node (ref "U$5") (pin "P$3") (pinfunction "GND_P$3") (pintype "bidirectional"))
      (node (ref "U$6") (pin "P$10") (pinfunction "RSVD_P$10") (pintype "bidirectional"))
      (node (ref "U$6") (pin "P$12") (pinfunction "GND$1_P$12") (pintype "bidirectional"))
      (node (ref "U$6") (pin "P$13") (pinfunction "GND$3_P$13") (pintype "bidirectional"))
      (node (ref "U$6") (pin "P$16") (pinfunction "GND$2_P$16") (pintype "bidirectional"))
      (node (ref "U$6") (pin "P$5") (pinfunction "GND$0_P$5") (pintype "bidirectional"))
      (node (ref "U$7") (pin "P$7") (pinfunction "GND_P$7") (pintype "bidirectional"))
      (node (ref "U$8") (pin "P$2") (pinfunction "GND$0_P$2") (pintype "bidirectional"))
      (node (ref "U$8") (pin "P$5") (pinfunction "GND$1_P$5") (pintype "bidirectional"))
      (node (ref "U$9") (pin "P$10") (pinfunction "RES_P$10") (pintype "bidirectional"))
      (node (ref "U$9") (pin "P$12") (pinfunction "GND$1_P$12") (pintype "bidirectional"))
      (node (ref "U$9") (pin "P$5") (pinfunction "GND$0_P$5") (pintype "bidirectional"))
    )
    (net (code "21") (name "INT-ADT7310") (class "Default")
      (node (ref "R9") (pin "1") (pinfunction "1_1") (pintype "passive"))
      (node (ref "U$7") (pin "P$5") (pinfunction "INT_P$5") (pintype "bidirectional"))
    )
    (net (code "22") (name "INT1-ADXL362") (class "Default")
      (node (ref "U$10") (pin "P$11") (pinfunction "INT1_P$11") (pintype "bidirectional"))
    )
    (net (code "23") (name "INT1-FXAS") (class "Default")
      (node (ref "U$2") (pin "P$3") (pinfunction "INT1_P$3") (pintype "bidirectional"))
    )
    (net (code "24") (name "INT1-L3GD") (class "Default")
      (node (ref "U$3") (pin "P$7") (pinfunction "INT1_P$7") (pintype "bidirectional"))
    )
    (net (code "25") (name "INT1-LIS3DH") (class "Default")
      (node (ref "U$9") (pin "P$11") (pinfunction "INT1_P$11") (pintype "bidirectional"))
    )
    (net (code "26") (name "INT1-LSM303") (class "Default")
      (node (ref "U$6") (pin "P$11") (pinfunction "INT1_P$11") (pintype "bidirectional"))
    )
    (net (code "27") (name "INT1-MAG3110") (class "Default")
      (node (ref "U$1") (pin "P$9") (pinfunction "INT1_P$9") (pintype "bidirectional"))
    )
    (net (code "28") (name "INT1-MPL311") (class "Default")
      (node (ref "U$5") (pin "P$6") (pinfunction "INT1_P$6") (pintype "bidirectional"))
    )
    (net (code "29") (name "LSM9D-DEN-G") (class "Default")
      (node (ref "U$17") (pin "P$10") (pinfunction "DEN_G_P$10") (pintype "bidirectional"))
    )
    (net (code "30") (name "LSM9D-DRGY-G") (class "Default")
      (node (ref "U$17") (pin "P$12") (pinfunction "DRDY_G_P$12") (pintype "bidirectional"))
    )
    (net (code "31") (name "LSM9D-INT-G") (class "Default")
      (node (ref "U$17") (pin "P$11") (pinfunction "INT_G_P$11") (pintype "bidirectional"))
    )
    (net (code "32") (name "LSM9D-INT1-XM") (class "Default")
      (node (ref "U$17") (pin "P$13") (pinfunction "INT1_XM_P$13") (pintype "bidirectional"))
    )
    (net (code "33") (name "MISO-A") (class "Default")
      (node (ref "U$11") (pin "P$28") (pinfunction "PF0_P$28") (pintype "bidirectional"))
      (node (ref "U$14") (pin "P$4") (pinfunction "A3_P$4") (pintype "bidirectional"))
    )
    (net (code "34") (name "MISO-B") (class "Default")
      (node (ref "TP2") (pin "P$1") (pinfunction "P$1_P$1") (pintype "bidirectional"))
      (node (ref "U$10") (pin "P$7") (pinfunction "MISO_P$7") (pintype "bidirectional"))
      (node (ref "U$14") (pin "P$17") (pinfunction "B3_P$17") (pintype "bidirectional"))
      (node (ref "U$17") (pin "P$22") (pinfunction "SDO_G_P$22") (pintype "bidirectional"))
      (node (ref "U$17") (pin "P$23") (pinfunction "SDO_XM_P$23") (pintype "bidirectional"))
      (node (ref "U$2") (pin "P$13") (pinfunction "MISO_P$13") (pintype "bidirectional"))
      (node (ref "U$3") (pin "P$4") (pinfunction "MISO_P$4") (pintype "bidirectional"))
      (node (ref "U$4") (pin "P$7") (pinfunction "MISO_P$7") (pintype "bidirectional"))
      (node (ref "U$6") (pin "P$7") (pinfunction "MISO_P$7") (pintype "bidirectional"))
      (node (ref "U$7") (pin "P$2") (pinfunction "DOUT_P$2") (pintype "bidirectional"))
      (node (ref "U$9") (pin "P$7") (pinfunction "MISO_P$7") (pintype "bidirectional"))
    )
    (net (code "35") (name "MOSI-A") (class "Default")
      (node (ref "U$11") (pin "P$29") (pinfunction "PF1_P$29") (pintype "bidirectional"))
      (node (ref "U$14") (pin "P$3") (pinfunction "A2_P$3") (pintype "bidirectional"))
    )
    (net (code "36") (name "MOSI-B") (class "Default")
      (node (ref "TP1") (pin "P$1") (pinfunction "P$1_P$1") (pintype "bidirectional"))
      (node (ref "U$10") (pin "P$6") (pinfunction "MOSI_P$6") (pintype "bidirectional"))
      (node (ref "U$14") (pin "P$18") (pinfunction "B2_P$18") (pintype "bidirectional"))
      (node (ref "U$17") (pin "P$24") (pinfunction "SDA_P$24") (pintype "bidirectional"))
      (node (ref "U$2") (pin "P$12") (pinfunction "MOSI_P$12") (pintype "bidirectional"))
      (node (ref "U$3") (pin "P$3") (pinfunction "MOSI_P$3") (pintype "bidirectional"))
      (node (ref "U$4") (pin "P$6") (pinfunction "MOSI_P$6") (pintype "bidirectional"))
      (node (ref "U$6") (pin "P$6") (pinfunction "MOSI_P$6") (pintype "bidirectional"))
      (node (ref "U$7") (pin "P$3") (pinfunction "DIN_P$3") (pintype "bidirectional"))
      (node (ref "U$9") (pin "P$6") (pinfunction "MOSI_P$6") (pintype "bidirectional"))
    )
    (net (code "37") (name "N$25") (class "Default")
      (node (ref "C15") (pin "1") (pinfunction "1_1") (pintype "passive"))
      (node (ref "C16") (pin "1") (pinfunction "1_1") (pintype "passive"))
      (node (ref "U$5") (pin "P$1") (pinfunction "VDD_P$1") (pintype "bidirectional"))
    )
    (net (code "38") (name "Net-(BAT1-+)") (class "Default")
      (node (ref "BAT1") (pin "1") (pinfunction "+_1") (pintype "power_in"))
      (node (ref "S1") (pin "2") (pinfunction "P_2") (pintype "passive"))
    )
    (net (code "39") (name "Net-(C24-Pad2)") (class "Default")
      (node (ref "C24") (pin "2") (pinfunction "2_2") (pintype "passive"))
      (node (ref "R10") (pin "1") (pinfunction "1_1") (pintype "passive"))
    )
    (net (code "40") (name "Net-(C43-Pad1)") (class "Default")
      (node (ref "C43") (pin "1") (pinfunction "1_1") (pintype "passive"))
      (node (ref "R16") (pin "2") (pinfunction "2_2") (pintype "passive"))
      (node (ref "U$13") (pin "P$1") (pinfunction "P$1_P$1") (pintype "bidirectional"))
    )
    (net (code "41") (name "Net-(IC1A-IN)") (class "Default")
      (node (ref "IC1") (pin "1") (pinfunction "IN_1") (pintype "input"))
      (node (ref "IC2") (pin "1") (pinfunction "IN_1") (pintype "input"))
      (node (ref "IC3") (pin "1") (pinfunction "IN_1") (pintype "input"))
      (node (ref "IC4") (pin "1") (pinfunction "IN_1") (pintype "input"))
      (node (ref "S1") (pin "3") (pinfunction "S_3") (pintype "passive"))
    )
    (net (code "42") (name "Net-(LED1-PadA)") (class "Default")
      (node (ref "LED1") (pin "A") (pinfunction "A_A") (pintype "passive"))
      (node (ref "R7") (pin "1") (pinfunction "1_1") (pintype "passive"))
    )
    (net (code "43") (name "Net-(U$1-CAP-A)") (class "Default")
      (node (ref "C1") (pin "1") (pinfunction "1_1") (pintype "passive"))
      (node (ref "U$1") (pin "P$1") (pinfunction "CAP-A_P$1") (pintype "bidirectional"))
    )
    (net (code "44") (name "Net-(U$1-CAP-R)") (class "Default")
      (node (ref "C4") (pin "1") (pinfunction "1_1") (pintype "passive"))
      (node (ref "U$1") (pin "P$4") (pinfunction "CAP-R_P$4") (pintype "bidirectional"))
    )
    (net (code "45") (name "Net-(U$2-VREGD)") (class "Default")
      (node (ref "C7") (pin "1") (pinfunction "1_1") (pintype "passive"))
      (node (ref "U$2") (pin "P$16") (pinfunction "VREGD_P$16") (pintype "bidirectional"))
    )
    (net (code "46") (name "Net-(U$3-CAP)") (class "Default")
      (node (ref "C10") (pin "1") (pinfunction "1_1") (pintype "passive"))
      (node (ref "U$3") (pin "P$14") (pinfunction "CAP_P$14") (pintype "bidirectional"))
    )
    (net (code "47") (name "Net-(U$5-CAP)") (class "Default")
      (node (ref "C17") (pin "1") (pinfunction "1_1") (pintype "passive"))
      (node (ref "U$5") (pin "P$2") (pinfunction "CAP_P$2") (pintype "bidirectional"))
    )
    (net (code "48") (name "Net-(U$6-C1)") (class "Default")
      (node (ref "C18") (pin "1") (pinfunction "1_1") (pintype "passive"))
      (node (ref "U$6") (pin "P$15") (pinfunction "C1_P$15") (pintype "bidirectional"))
    )
    (net (code "49") (name "Net-(U$6-SETC)") (class "Default")
      (node (ref "C21") (pin "2") (pinfunction "2_2") (pintype "passive"))
      (node (ref "U$6") (pin "P$2") (pinfunction "SETC_P$2") (pintype "bidirectional"))
    )
    (net (code "50") (name "Net-(U$6-SETP)") (class "Default")
      (node (ref "C21") (pin "1") (pinfunction "1_1") (pintype "passive"))
      (node (ref "U$6") (pin "P$3") (pinfunction "SETP_P$3") (pintype "bidirectional"))
    )
    (net (code "51") (name "Net-(U$11-GNDX)") (class "Default")
      (node (ref "C41") (pin "2") (pinfunction "2_2") (pintype "passive"))
      (node (ref "C42") (pin "1") (pinfunction "1_1") (pintype "passive"))
      (node (ref "U$11") (pin "P$35") (pinfunction "GNDX_P$35") (pintype "bidirectional"))
    )
    (net (code "52") (name "Net-(U$11-OSC0)") (class "Default")
      (node (ref "C44") (pin "1") (pinfunction "1_1") (pintype "passive"))
      (node (ref "U$11") (pin "P$40") (pinfunction "OSC0_P$40") (pintype "bidirectional"))
      (node (ref "U$13") (pin "P$2") (pinfunction "P$2_P$2") (pintype "bidirectional"))
    )
    (net (code "53") (name "Net-(U$11-OSC1)") (class "Default")
      (node (ref "R16") (pin "1") (pinfunction "1_1") (pintype "passive"))
      (node (ref "U$11") (pin "P$41") (pinfunction "OSC1_P$41") (pintype "bidirectional"))
    )
    (net (code "54") (name "Net-(U$11-XOSC1)") (class "Default")
      (node (ref "C42") (pin "2") (pinfunction "2_2") (pintype "passive"))
      (node (ref "U$11") (pin "P$36") (pinfunction "XOSC1_P$36") (pintype "bidirectional"))
      (node (ref "U$12") (pin "P$2") (pinfunction "P$2_P$2") (pintype "bidirectional"))
    )
    (net (code "55") (name "Net-(U$11-XOSCO)") (class "Default")
      (node (ref "C41") (pin "1") (pinfunction "1_1") (pintype "passive"))
      (node (ref "U$11") (pin "P$34") (pinfunction "XOSCO_P$34") (pintype "bidirectional"))
      (node (ref "U$12") (pin "P$1") (pinfunction "P$1_P$1") (pintype "bidirectional"))
    )
    (net (code "56") (name "Net-(U$11-~{RST})") (class "Default")
      (node (ref "C30") (pin "2") (pinfunction "2_2") (pintype "passive"))
      (node (ref "R17") (pin "1") (pinfunction "1_1") (pintype "passive"))
      (node (ref "U$11") (pin "P$38") (pinfunction "~{RST}_P$38") (pintype "bidirectional"))
    )
    (net (code "57") (name "Net-(U$11-~{WAKE})") (class "Default")
      (node (ref "R15") (pin "1") (pinfunction "1_1") (pintype "passive"))
      (node (ref "U$11") (pin "P$32") (pinfunction "~{WAKE}_P$32") (pintype "bidirectional"))
    )
    (net (code "58") (name "Net-(U$17-C1_XM)") (class "Default")
      (node (ref "C48") (pin "1") (pinfunction "1_1") (pintype "passive"))
      (node (ref "U$17") (pin "P$7") (pinfunction "C1_XM_P$7") (pintype "bidirectional"))
    )
    (net (code "59") (name "Net-(U$17-SETC_XM)") (class "Default")
      (node (ref "C49") (pin "2") (pinfunction "2_2") (pintype "passive"))
      (node (ref "U$17") (pin "P$8") (pinfunction "SETC_XM_P$8") (pintype "bidirectional"))
    )
    (net (code "60") (name "Net-(U$17-SETP_XM)") (class "Default")
      (node (ref "C49") (pin "1") (pinfunction "1_1") (pintype "passive"))
      (node (ref "U$17") (pin "P$9") (pinfunction "SETP_XM_P$9") (pintype "bidirectional"))
    )
    (net (code "61") (name "RST_B") (class "Default")
      (node (ref "R5") (pin "1") (pinfunction "1_1") (pintype "passive"))
      (node (ref "U$2") (pin "P$4") (pinfunction "RST_B_P$4") (pintype "bidirectional"))
    )
    (net (code "62") (name "SCL-0") (class "Default")
      (node (ref "R1") (pin "1") (pinfunction "1_1") (pintype "passive"))
      (node (ref "TP6") (pin "P$1") (pinfunction "P$1_P$1") (pintype "bidirectional"))
      (node (ref "U$1") (pin "P$7") (pinfunction "SCL_P$7") (pintype "bidirectional"))
      (node (ref "U$11") (pin "P$23") (pinfunction "PA6_P$23") (pintype "bidirectional"))
      (node (ref "U$5") (pin "P$8") (pinfunction "SCL_P$8") (pintype "bidirectional"))
    )
    (net (code "63") (name "SCLK-A") (class "Default")
      (node (ref "U$11") (pin "P$30") (pinfunction "PF2_P$30") (pintype "bidirectional"))
      (node (ref "U$14") (pin "P$5") (pinfunction "A4_P$5") (pintype "bidirectional"))
    )
    (net (code "64") (name "SCLK-B") (class "Default")
      (node (ref "TP3") (pin "P$1") (pinfunction "P$1_P$1") (pintype "bidirectional"))
      (node (ref "U$10") (pin "P$4") (pinfunction "SCLK_P$4") (pintype "bidirectional"))
      (node (ref "U$14") (pin "P$16") (pinfunction "B4_P$16") (pintype "bidirectional"))
      (node (ref "U$17") (pin "P$21") (pinfunction "SCL_P$21") (pintype "bidirectional"))
      (node (ref "U$2") (pin "P$11") (pinfunction "SCLK_P$11") (pintype "bidirectional"))
      (node (ref "U$3") (pin "P$2") (pinfunction "SCL_P$2") (pintype "bidirectional"))
      (node (ref "U$4") (pin "P$4") (pinfunction "SCL_P$4") (pintype "bidirectional"))
      (node (ref "U$6") (pin "P$4") (pinfunction "SCL_P$4") (pintype "bidirectional"))
      (node (ref "U$7") (pin "P$1") (pinfunction "SCLK_P$1") (pintype "bidirectional"))
      (node (ref "U$9") (pin "P$4") (pinfunction "SCL_P$4") (pintype "bidirectional"))
    )
    (net (code "65") (name "SD-CARD-INSERT") (class "Default")
      (node (ref "U$11") (pin "P$60") (pinfunction "PE5_P$60") (pintype "bidirectional"))
      (node (ref "U$18") (pin "P$8") (pinfunction "SWITCH2_P$8") (pintype "bidirectional"))
    )
    (net (code "66") (name "SD-CS") (class "Default")
      (node (ref "R6") (pin "1") (pinfunction "1_1") (pintype "passive"))
      (node (ref "U$11") (pin "P$62") (pinfunction "PD1_P$62") (pintype "bidirectional"))
      (node (ref "U$18") (pin "P$2") (pinfunction "CS_P$2") (pintype "bidirectional"))
    )
    (net (code "67") (name "SD-MISO") (class "Default")
      (node (ref "U$11") (pin "P$63") (pinfunction "PD2_P$63") (pintype "bidirectional"))
      (node (ref "U$18") (pin "P$7") (pinfunction "D0_P$7") (pintype "bidirectional"))
    )
    (net (code "68") (name "SD-MOSI") (class "Default")
      (node (ref "U$11") (pin "P$64") (pinfunction "PD3_P$64") (pintype "bidirectional"))
      (node (ref "U$18") (pin "P$3") (pinfunction "DI_P$3") (pintype "bidirectional"))
    )
    (net (code "69") (name "SD-SCLK") (class "Default")
      (node (ref "U$11") (pin "P$61") (pinfunction "PD0_P$61") (pintype "bidirectional"))
      (node (ref "U$18") (pin "P$5") (pinfunction "SCLK_P$5") (pintype "bidirectional"))
    )
    (net (code "70") (name "SDA-0") (class "Default")
      (node (ref "R2") (pin "1") (pinfunction "1_1") (pintype "passive"))
      (node (ref "TP5") (pin "P$1") (pinfunction "P$1_P$1") (pintype "bidirectional"))
      (node (ref "U$1") (pin "P$6") (pinfunction "SDA_P$6") (pintype "bidirectional"))
      (node (ref "U$11") (pin "P$24") (pinfunction "PA7_P$24") (pintype "bidirectional"))
      (node (ref "U$5") (pin "P$7") (pinfunction "SDA_P$7") (pintype "bidirectional"))
    )
    (net (code "71") (name "SPI-ADDR0") (class "Default")
      (node (ref "U$11") (pin "P$16") (pinfunction "PC4_P$16") (pintype "bidirectional"))
      (node (ref "U$15") (pin "P$1") (pinfunction "A0_P$1") (pintype "bidirectional"))
    )
    (net (code "72") (name "SPI-ADDR1") (class "Default")
      (node (ref "U$11") (pin "P$15") (pinfunction "PC5_P$15") (pintype "bidirectional"))
      (node (ref "U$15") (pin "P$2") (pinfunction "A1_P$2") (pintype "bidirectional"))
    )
    (net (code "73") (name "SPI-ADDR2") (class "Default")
      (node (ref "U$11") (pin "P$14") (pinfunction "PC6_P$14") (pintype "bidirectional"))
      (node (ref "U$15") (pin "P$3") (pinfunction "A2_P$3") (pintype "bidirectional"))
    )
    (net (code "74") (name "SPI-ENABLE") (class "Default")
      (node (ref "U$11") (pin "P$31") (pinfunction "PF3_P$31") (pintype "bidirectional"))
      (node (ref "U$14") (pin "P$10") (pinfunction "OE_P$10") (pintype "bidirectional"))
    )
    (net (code "75") (name "SWCLK") (class "Default")
      (node (ref "U$11") (pin "P$52") (pinfunction "PC0_P$52") (pintype "bidirectional"))
      (node (ref "X3") (pin "4") (pinfunction "S_4") (pintype "passive"))
    )
    (net (code "76") (name "SWDIO") (class "Default")
      (node (ref "U$11") (pin "P$51") (pinfunction "PC1_P$51") (pintype "bidirectional"))
      (node (ref "X3") (pin "3") (pinfunction "S_3") (pintype "passive"))
    )
    (net (code "77") (name "SWO") (class "Default")
      (node (ref "U$11") (pin "P$49") (pinfunction "PC3_P$49") (pintype "bidirectional"))
      (node (ref "X3") (pin "1") (pinfunction "S_1") (pintype "passive"))
    )
    (net (code "78") (name "TDI") (class "Default")
      (node (ref "U$11") (pin "P$50") (pinfunction "PC2_P$50") (pintype "bidirectional"))
      (node (ref "X3") (pin "2") (pinfunction "S_2") (pintype "passive"))
    )
    (net (code "79") (name "U0RX") (class "Default")
      (node (ref "U$11") (pin "P$17") (pinfunction "PA0_P$17") (pintype "bidirectional"))
    )
    (net (code "80") (name "U0TX") (class "Default")
      (node (ref "U$11") (pin "P$18") (pinfunction "PA1_P$18") (pintype "bidirectional"))
    )
    (net (code "81") (name "U1RX") (class "Default")
      (node (ref "TP8") (pin "P$1") (pinfunction "P$1_P$1") (pintype "bidirectional"))
      (node (ref "U$11") (pin "P$45") (pinfunction "PB0_P$45") (pintype "bidirectional"))
    )
    (net (code "82") (name "U1TX") (class "Default")
      (node (ref "TP7") (pin "P$1") (pinfunction "P$1_P$1") (pintype "bidirectional"))
      (node (ref "U$11") (pin "P$46") (pinfunction "PB1_P$46") (pintype "bidirectional"))
    )
    (net (code "83") (name "unconnected-(S1-O-Pad1)") (class "Default")
      (node (ref "S1") (pin "1") (pinfunction "O_1") (pintype "passive"))
    )
    (net (code "84") (name "unconnected-(U$1-NC-PadP$3)") (class "Default")
      (node (ref "U$1") (pin "P$3") (pinfunction "NC_P$3") (pintype "bidirectional"))
    )
    (net (code "85") (name "unconnected-(U$2-INT2-PadP$2)") (class "Default")
      (node (ref "U$2") (pin "P$2") (pinfunction "INT2_P$2") (pintype "bidirectional"))
    )
    (net (code "86") (name "unconnected-(U$3-INT2-PadP$6)") (class "Default")
      (node (ref "U$3") (pin "P$6") (pinfunction "INT2_P$6") (pintype "bidirectional"))
    )
    (net (code "87") (name "unconnected-(U$4-INT2-PadP$9)") (class "Default")
      (node (ref "U$4") (pin "P$9") (pinfunction "INT2_P$9") (pintype "bidirectional"))
    )
    (net (code "88") (name "unconnected-(U$4-NC$0-PadP$2)") (class "Default")
      (node (ref "U$4") (pin "P$2") (pinfunction "NC$0_P$2") (pintype "bidirectional"))
    )
    (net (code "89") (name "unconnected-(U$4-NC$1-PadP$3)") (class "Default")
      (node (ref "U$4") (pin "P$3") (pinfunction "NC$1_P$3") (pintype "bidirectional"))
    )
    (net (code "90") (name "unconnected-(U$5-INT2-PadP$5)") (class "Default")
      (node (ref "U$5") (pin "P$5") (pinfunction "INT2_P$5") (pintype "bidirectional"))
    )
    (net (code "91") (name "unconnected-(U$6-INT2-PadP$9)") (class "Default")
      (node (ref "U$6") (pin "P$9") (pinfunction "INT2_P$9") (pintype "bidirectional"))
    )
    (net (code "92") (name "unconnected-(U$8-NC-PadP$1)") (class "Default")
      (node (ref "U$8") (pin "P$1") (pinfunction "NC_P$1") (pintype "bidirectional"))
    )
    (net (code "93") (name "unconnected-(U$9-ADC1-PadP$16)") (class "Default")
      (node (ref "U$9") (pin "P$16") (pinfunction "ADC1_P$16") (pintype "bidirectional"))
    )
    (net (code "94") (name "unconnected-(U$9-ADC2-PadP$15)") (class "Default")
      (node (ref "U$9") (pin "P$15") (pinfunction "ADC2_P$15") (pintype "bidirectional"))
    )
    (net (code "95") (name "unconnected-(U$9-ADC3-PadP$13)") (class "Default")
      (node (ref "U$9") (pin "P$13") (pinfunction "ADC3_P$13") (pintype "bidirectional"))
    )
    (net (code "96") (name "unconnected-(U$9-INT2-PadP$9)") (class "Default")
      (node (ref "U$9") (pin "P$9") (pinfunction "INT2_P$9") (pintype "bidirectional"))
    )
    (net (code "97") (name "unconnected-(U$9-NC$0-PadP$2)") (class "Default")
      (node (ref "U$9") (pin "P$2") (pinfunction "NC$0_P$2") (pintype "bidirectional"))
    )
    (net (code "98") (name "unconnected-(U$9-NC$1-PadP$3)") (class "Default")
      (node (ref "U$9") (pin "P$3") (pinfunction "NC$1_P$3") (pintype "bidirectional"))
    )
    (net (code "99") (name "unconnected-(U$10-INT2-PadP$9)") (class "Default")
      (node (ref "U$10") (pin "P$9") (pinfunction "INT2_P$9") (pintype "bidirectional"))
    )
    (net (code "100") (name "unconnected-(U$10-NC$0-PadP$2)") (class "Default")
      (node (ref "U$10") (pin "P$2") (pinfunction "NC$0_P$2") (pintype "bidirectional"))
    )
    (net (code "101") (name "unconnected-(U$10-NC$1-PadP$15)") (class "Default")
      (node (ref "U$10") (pin "P$15") (pinfunction "NC$1_P$15") (pintype "bidirectional"))
    )
    (net (code "102") (name "unconnected-(U$10-RSVD$0-PadP$3)") (class "Default")
      (node (ref "U$10") (pin "P$3") (pinfunction "RSVD$0_P$3") (pintype "bidirectional"))
    )
    (net (code "103") (name "unconnected-(U$10-RSVD$1-PadP$5)") (class "Default")
      (node (ref "U$10") (pin "P$5") (pinfunction "RSVD$1_P$5") (pintype "bidirectional"))
    )
    (net (code "104") (name "unconnected-(U$10-RSVD$2-PadP$10)") (class "Default")
      (node (ref "U$10") (pin "P$10") (pinfunction "RSVD$2_P$10") (pintype "bidirectional"))
    )
    (net (code "105") (name "unconnected-(U$11-PA2-PadP$19)") (class "Default")
      (node (ref "U$11") (pin "P$19") (pinfunction "PA2_P$19") (pintype "bidirectional"))
    )
    (net (code "106") (name "unconnected-(U$11-PA3-PadP$20)") (class "Default")
      (node (ref "U$11") (pin "P$20") (pinfunction "PA3_P$20") (pintype "bidirectional"))
    )
    (net (code "107") (name "unconnected-(U$11-PA4-PadP$21)") (class "Default")
      (node (ref "U$11") (pin "P$21") (pinfunction "PA4_P$21") (pintype "bidirectional"))
    )
    (net (code "108") (name "unconnected-(U$11-PA5-PadP$22)") (class "Default")
      (node (ref "U$11") (pin "P$22") (pinfunction "PA5_P$22") (pintype "bidirectional"))
    )
    (net (code "109") (name "unconnected-(U$11-PB2-PadP$47)") (class "Default")
      (node (ref "U$11") (pin "P$47") (pinfunction "PB2_P$47") (pintype "bidirectional"))
    )
    (net (code "110") (name "unconnected-(U$11-PB3-PadP$48)") (class "Default")
      (node (ref "U$11") (pin "P$48") (pinfunction "PB3_P$48") (pintype "bidirectional"))
    )
    (net (code "111") (name "unconnected-(U$11-PB4-PadP$58)") (class "Default")
      (node (ref "U$11") (pin "P$58") (pinfunction "PB4_P$58") (pintype "bidirectional"))
    )
    (net (code "112") (name "unconnected-(U$11-PB5-PadP$57)") (class "Default")
      (node (ref "U$11") (pin "P$57") (pinfunction "PB5_P$57") (pintype "bidirectional"))
    )
    (net (code "113") (name "unconnected-(U$11-PB7-PadP$4)") (class "Default")
      (node (ref "U$11") (pin "P$4") (pinfunction "PB7_P$4") (pintype "bidirectional"))
    )
    (net (code "114") (name "unconnected-(U$11-PD4-PadP$43)") (class "Default")
      (node (ref "U$11") (pin "P$43") (pinfunction "PD4_P$43") (pintype "bidirectional"))
    )
    (net (code "115") (name "unconnected-(U$11-PD5-PadP$44)") (class "Default")
      (node (ref "U$11") (pin "P$44") (pinfunction "PD5_P$44") (pintype "bidirectional"))
    )
    (net (code "116") (name "unconnected-(U$11-PD6-PadP$53)") (class "Default")
      (node (ref "U$11") (pin "P$53") (pinfunction "PD6_P$53") (pintype "bidirectional"))
    )
    (net (code "117") (name "unconnected-(U$11-PD7-PadP$10)") (class "Default")
      (node (ref "U$11") (pin "P$10") (pinfunction "PD7_P$10") (pintype "bidirectional"))
    )
    (net (code "118") (name "unconnected-(U$11-PE0-PadP$9)") (class "Default")
      (node (ref "U$11") (pin "P$9") (pinfunction "PE0_P$9") (pintype "bidirectional"))
    )
    (net (code "119") (name "unconnected-(U$11-PE1-PadP$8)") (class "Default")
      (node (ref "U$11") (pin "P$8") (pinfunction "PE1_P$8") (pintype "bidirectional"))
    )
    (net (code "120") (name "unconnected-(U$11-PE2-PadP$7)") (class "Default")
      (node (ref "U$11") (pin "P$7") (pinfunction "PE2_P$7") (pintype "bidirectional"))
    )
    (net (code "121") (name "unconnected-(U$11-PE4-PadP$59)") (class "Default")
      (node (ref "U$11") (pin "P$59") (pinfunction "PE4_P$59") (pintype "bidirectional"))
    )
    (net (code "122") (name "unconnected-(U$11-PF4-PadP$5)") (class "Default")
      (node (ref "U$11") (pin "P$5") (pinfunction "PF4_P$5") (pintype "bidirectional"))
    )
    (net (code "123") (name "unconnected-(U$11-~{HIB}-PadP$33)") (class "Default")
      (node (ref "U$11") (pin "P$33") (pinfunction "~{HIB}_P$33") (pintype "bidirectional"))
    )
    (net (code "124") (name "unconnected-(U$14-A1-PadP$1)") (class "Default")
      (node (ref "U$14") (pin "P$1") (pinfunction "A1_P$1") (pintype "bidirectional"))
    )
    (net (code "125") (name "unconnected-(U$14-A5-PadP$6)") (class "Default")
      (node (ref "U$14") (pin "P$6") (pinfunction "A5_P$6") (pintype "bidirectional"))
    )
    (net (code "126") (name "unconnected-(U$14-A6-PadP$7)") (class "Default")
      (node (ref "U$14") (pin "P$7") (pinfunction "A6_P$7") (pintype "bidirectional"))
    )
    (net (code "127") (name "unconnected-(U$14-A7-PadP$8)") (class "Default")
      (node (ref "U$14") (pin "P$8") (pinfunction "A7_P$8") (pintype "bidirectional"))
    )
    (net (code "128") (name "unconnected-(U$14-A8-PadP$9)") (class "Default")
      (node (ref "U$14") (pin "P$9") (pinfunction "A8_P$9") (pintype "bidirectional"))
    )
    (net (code "129") (name "unconnected-(U$14-B1-PadP$20)") (class "Default")
      (node (ref "U$14") (pin "P$20") (pinfunction "B1_P$20") (pintype "bidirectional"))
    )
    (net (code "130") (name "unconnected-(U$14-B5-PadP$15)") (class "Default")
      (node (ref "U$14") (pin "P$15") (pinfunction "B5_P$15") (pintype "bidirectional"))
    )
    (net (code "131") (name "unconnected-(U$14-B6-PadP$14)") (class "Default")
      (node (ref "U$14") (pin "P$14") (pinfunction "B6_P$14") (pintype "bidirectional"))
    )
    (net (code "132") (name "unconnected-(U$14-B7-PadP$13)") (class "Default")
      (node (ref "U$14") (pin "P$13") (pinfunction "B7_P$13") (pintype "bidirectional"))
    )
    (net (code "133") (name "unconnected-(U$14-B8-PadP$12)") (class "Default")
      (node (ref "U$14") (pin "P$12") (pinfunction "B8_P$12") (pintype "bidirectional"))
    )
    (net (code "134") (name "unconnected-(U$16-NC#0-PadP$1)") (class "Default")
      (node (ref "U$16") (pin "P$1") (pinfunction "NC#0_P$1") (pintype "bidirectional"))
    )
    (net (code "135") (name "unconnected-(U$16-NC#1-PadP$2)") (class "Default")
      (node (ref "U$16") (pin "P$2") (pinfunction "NC#1_P$2") (pintype "bidirectional"))
    )
    (net (code "136") (name "unconnected-(U$16-NC#2-PadP$5)") (class "Default")
      (node (ref "U$16") (pin "P$5") (pinfunction "NC#2_P$5") (pintype "bidirectional"))
    )
    (net (code "137") (name "unconnected-(U$17-INT2_XM-PadP$14)") (class "Default")
      (node (ref "U$17") (pin "P$14") (pinfunction "INT2_XM_P$14") (pintype "bidirectional"))
    )
    (net (code "138") (name "unconnected-(U$17-RES#0-PadP$1)") (class "Default")
      (node (ref "U$17") (pin "P$1") (pinfunction "RES#0_P$1") (pintype "bidirectional"))
    )
    (net (code "139") (name "unconnected-(U$18-GND#1-PadP$10)") (class "Default")
      (node (ref "U$18") (pin "P$10") (pinfunction "GND#1_P$10") (pintype "bidirectional"))
    )
    (net (code "140") (name "unconnected-(U$18-GND#2-PadP$11)") (class "Default")
      (node (ref "U$18") (pin "P$11") (pinfunction "GND#2_P$11") (pintype "bidirectional"))
    )
    (net (code "141") (name "unconnected-(U$18-GND#3-PadP$12)") (class "Default")
      (node (ref "U$18") (pin "P$12") (pinfunction "GND#3_P$12") (pintype "bidirectional"))
    )
    (net (code "142") (name "unconnected-(U$18-GND#4-PadP$13)") (class "Default")
      (node (ref "U$18") (pin "P$13") (pinfunction "GND#4_P$13") (pintype "bidirectional"))
    )
    (net (code "143") (name "unconnected-(U$18-RSV-PadP$1)") (class "Default")
      (node (ref "U$18") (pin "P$1") (pinfunction "RSV_P$1") (pintype "bidirectional"))
    )
  )
)
